# design.net
KiCad netlist of a schematic drawn in EasyEDA Pro
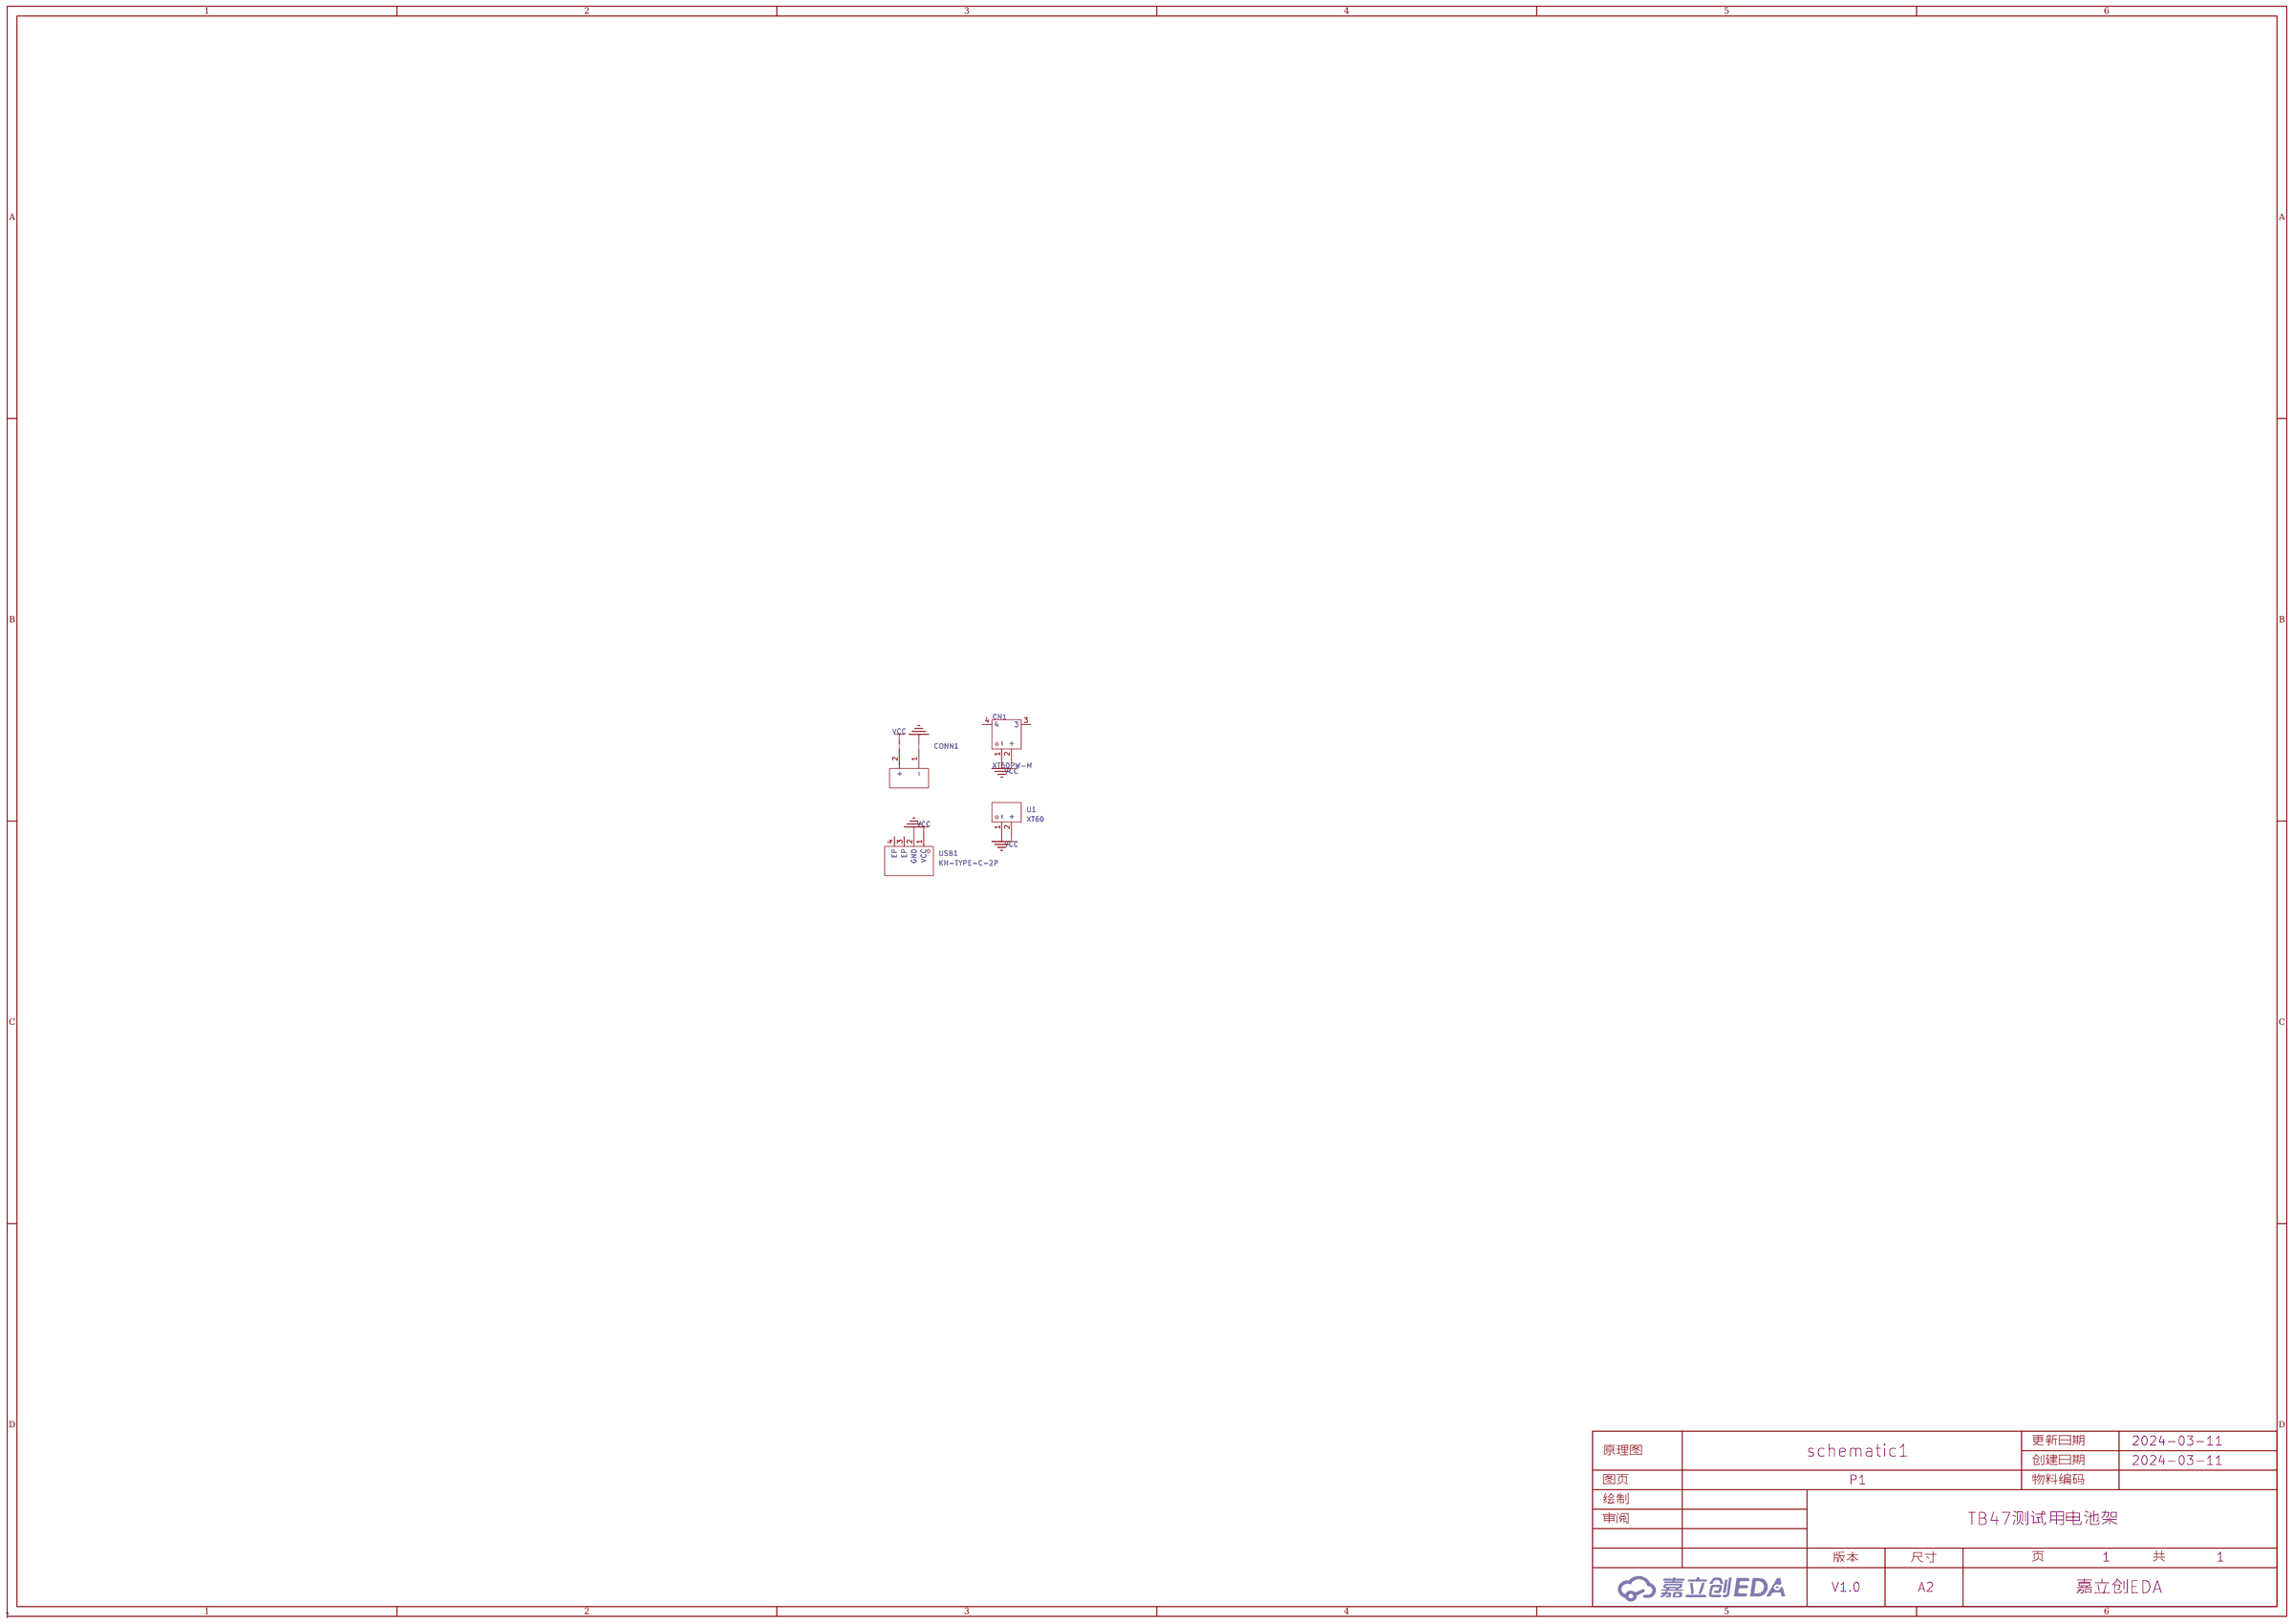
[diagram p0: schematic sheet]

(export (version "E")
  (design (tool "Eeschema 10.0.6"))
  (components
    (comp (ref "CN1")
      (value "XT60PW-M")
      (footprint "easyedapro:CONN-TH_XT60PW-M")
      (description "类别:-;类型1:-;")
      (fields (field (name "Manufacturer") "AMASS(艾迈斯)"))
      (libsource (lib "easyedapro") (part "XT60PW-M"))
    )
    (comp (ref "CONN1")
      (value "~")
      (footprint "easyedapro:TB47金手指")
      (libsource (lib "easyedapro") (part "TB47金手指"))
    )
    (comp (ref "U1")
      (value "XT60")
      (footprint "easyedapro:CONN-TH_XT60")
      (description "类别:-;类型1:-;")
      (fields (field (name "Manufacturer") "AMASS(艾迈斯)"))
      (libsource (lib "easyedapro") (part "XT60"))
    )
    (comp (ref "USB1")
      (value "KH-TYPE-C-2P")
      (footprint "easyedapro:USB-SMD_KH-TYPE-C-2P")
      (description "连接器类型:Type-C;标准:-;公母:-;端口数量:-;触点数量:2P;安装方式:-;额定电流 - 电源:-;触头材质:-;触头镀层:-;工作温度范围:-;")
      (fields (field (name "Manufacturer") "kinghelm(金航标)"))
      (libsource (lib "easyedapro") (part "KH-TYPE-C-2P"))
    )
  )
  (nets
    (net (code "1") (name "GND") (class "Default")
      (node (ref "CN1") (pin "1") (pinfunction "-_1") (pintype "unspecified"))
      (node (ref "CONN1") (pin "1") (pinfunction "-_1") (pintype "input"))
      (node (ref "U1") (pin "1") (pinfunction "-_1") (pintype "input"))
      (node (ref "USB1") (pin "2") (pinfunction "GND_2") (pintype "unspecified"))
    )
    (net (code "2") (name "VCC") (class "Default")
      (node (ref "CN1") (pin "2") (pinfunction "+_2") (pintype "unspecified"))
      (node (ref "CONN1") (pin "2") (pinfunction "+_2") (pintype "input"))
      (node (ref "U1") (pin "2") (pinfunction "+_2") (pintype "input"))
      (node (ref "USB1") (pin "1") (pinfunction "VCC_1") (pintype "unspecified"))
    )
    (net (code "3") (name "unconnected-(CN1-Pad3)") (class "Default")
      (node (ref "CN1") (pin "3") (pinfunction "3_3") (pintype "unspecified"))
    )
    (net (code "4") (name "unconnected-(CN1-Pad4)") (class "Default")
      (node (ref "CN1") (pin "4") (pinfunction "4_4") (pintype "unspecified"))
    )
    (net (code "5") (name "unconnected-(USB1-EP-Pad3)") (class "Default")
      (node (ref "USB1") (pin "3") (pinfunction "EP_3") (pintype "unspecified"))
    )
    (net (code "6") (name "unconnected-(USB1-EP-Pad4)") (class "Default")
      (node (ref "USB1") (pin "4") (pinfunction "EP_4") (pintype "unspecified"))
    )
  )
)
